# yamaguchi.net
KiCad netlist of a schematic drawn in EAGLE
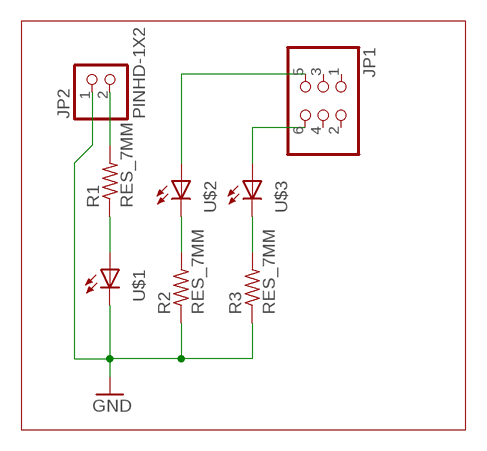
[diagram p0: schematic, sheet 1]

(export (version "E")
  (design (tool "Eeschema 10.0.6"))
  (components
    (comp (ref "JP1")
      (value "PINHD-2X3")
      (footprint "eagle-import:2X03")
      (libsource (lib "eagle-import") (part "PINHD-2X3"))
    )
    (comp (ref "JP2")
      (value "PINHD-1X2")
      (footprint "eagle-import:1X02")
      (libsource (lib "eagle-import") (part "PINHD-1X2"))
    )
    (comp (ref "R1")
      (value "RES_7MM")
      (footprint "eagle-import:0204_7")
      (libsource (lib "eagle-import") (part "RES_7MM"))
    )
    (comp (ref "R2")
      (value "RES_7MM")
      (footprint "eagle-import:0204_7")
      (libsource (lib "eagle-import") (part "RES_7MM"))
    )
    (comp (ref "R3")
      (value "RES_7MM")
      (footprint "eagle-import:0204_7")
      (libsource (lib "eagle-import") (part "RES_7MM"))
    )
    (comp (ref "U$1")
      (value "LED1206")
      (footprint "eagle-import:1206")
      (libsource (lib "eagle-import") (part "LED1206"))
    )
    (comp (ref "U$2")
      (value "LED1206")
      (footprint "eagle-import:1206")
      (libsource (lib "eagle-import") (part "LED1206"))
    )
    (comp (ref "U$3")
      (value "LED1206")
      (footprint "eagle-import:1206")
      (libsource (lib "eagle-import") (part "LED1206"))
    )
  )
  (nets
    (net (code "1") (name "GND") (class "Default")
      (node (ref "JP2") (pin "1") (pinfunction "1_1") (pintype "passive"))
      (node (ref "R2") (pin "1") (pinfunction "1_1") (pintype "passive"))
      (node (ref "R3") (pin "1") (pinfunction "1_1") (pintype "passive"))
      (node (ref "U$1") (pin "2") (pinfunction "C_2") (pintype "passive"))
    )
    (net (code "2") (name "Net-(JP2-Pad2)") (class "Default")
      (node (ref "JP2") (pin "2") (pinfunction "2_2") (pintype "passive"))
      (node (ref "R1") (pin "2") (pinfunction "2_2") (pintype "passive"))
    )
    (net (code "3") (name "Net-(U$1-A)") (class "Default")
      (node (ref "R1") (pin "1") (pinfunction "1_1") (pintype "passive"))
      (node (ref "U$1") (pin "1") (pinfunction "A_1") (pintype "passive"))
    )
    (net (code "4") (name "Net-(U$2-A)") (class "Default")
      (node (ref "JP1") (pin "5") (pinfunction "5_5") (pintype "passive"))
      (node (ref "U$2") (pin "1") (pinfunction "A_1") (pintype "passive"))
    )
    (net (code "5") (name "Net-(U$2-C)") (class "Default")
      (node (ref "R2") (pin "2") (pinfunction "2_2") (pintype "passive"))
      (node (ref "U$2") (pin "2") (pinfunction "C_2") (pintype "passive"))
    )
    (net (code "6") (name "Net-(U$3-A)") (class "Default")
      (node (ref "JP1") (pin "6") (pinfunction "6_6") (pintype "passive"))
      (node (ref "U$3") (pin "1") (pinfunction "A_1") (pintype "passive"))
    )
    (net (code "7") (name "Net-(U$3-C)") (class "Default")
      (node (ref "R3") (pin "2") (pinfunction "2_2") (pintype "passive"))
      (node (ref "U$3") (pin "2") (pinfunction "C_2") (pintype "passive"))
    )
    (net (code "8") (name "unconnected-(JP1-Pad1)") (class "Default")
      (node (ref "JP1") (pin "1") (pinfunction "1_1") (pintype "passive"))
    )
    (net (code "9") (name "unconnected-(JP1-Pad2)") (class "Default")
      (node (ref "JP1") (pin "2") (pinfunction "2_2") (pintype "passive"))
    )
    (net (code "10") (name "unconnected-(JP1-Pad3)") (class "Default")
      (node (ref "JP1") (pin "3") (pinfunction "3_3") (pintype "passive"))
    )
    (net (code "11") (name "unconnected-(JP1-Pad4)") (class "Default")
      (node (ref "JP1") (pin "4") (pinfunction "4_4") (pintype "passive"))
    )
  )
)
